# X8-Navboard.net
KiCad netlist of a schematic drawn in EAGLE
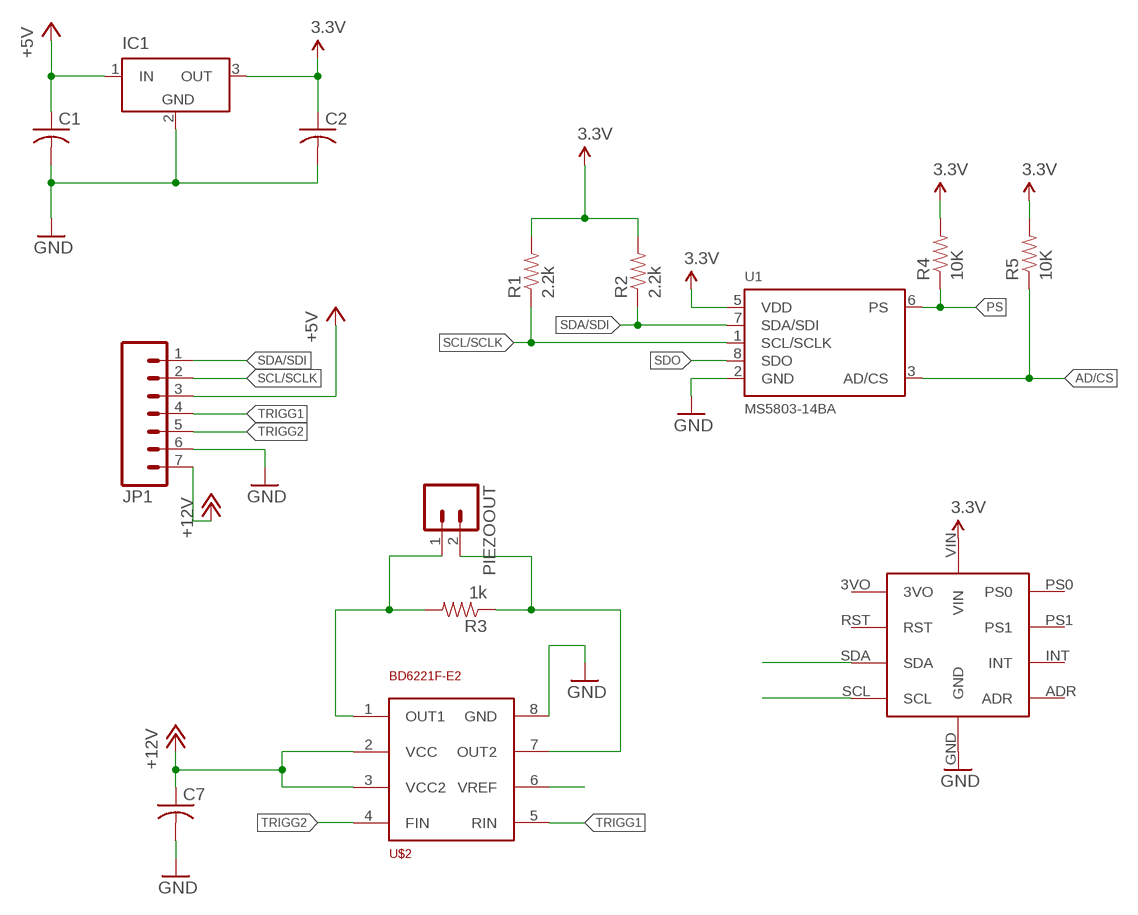
[diagram p0: schematic, sheet 1]

(export (version "E")
  (design (tool "Eeschema 10.0.6"))
  (components
    (comp (ref "C1")
      (value "C-USC0603")
      (footprint "eagle-import:C0603")
      (libsource (lib "eagle-import") (part "C-USC0603"))
    )
    (comp (ref "C2")
      (value "C-USC0603")
      (footprint "eagle-import:C0603")
      (libsource (lib "eagle-import") (part "C-USC0603"))
    )
    (comp (ref "C7")
      (value "C-USC0603")
      (footprint "eagle-import:C0603")
      (libsource (lib "eagle-import") (part "C-USC0603"))
    )
    (comp (ref "IC1")
      (value "LT1129CST5")
      (footprint "eagle-import:SOT223")
      (fields (field (name "MPN") "LT1129CST-5#PBF"))
      (libsource (lib "eagle-import") (part "LT1129CST5"))
    )
    (comp (ref "JP1")
      (value "M07")
      (footprint "eagle-import:1X07")
      (libsource (lib "eagle-import") (part "M07"))
    )
    (comp (ref "PIEZOOUT")
      (value "M02LOCK_LONGPADS")
      (footprint "eagle-import:1X02_LOCK_LONGPADS")
      (libsource (lib "eagle-import") (part "M02LOCK_LONGPADS"))
    )
    (comp (ref "R1")
      (value "2.2k")
      (footprint "eagle-import:0603-RES")
      (libsource (lib "eagle-import") (part "2.2KOHM1/10W1%(0603)"))
    )
    (comp (ref "R2")
      (value "2.2k")
      (footprint "eagle-import:0603-RES")
      (libsource (lib "eagle-import") (part "2.2KOHM1/10W1%(0603)"))
    )
    (comp (ref "R3")
      (value "1k")
      (footprint "eagle-import:0603-RES")
      (libsource (lib "eagle-import") (part "2.2KOHM1/10W1%(0603)"))
    )
    (comp (ref "R4")
      (value "10K")
      (footprint "eagle-import:0603-RES")
      (libsource (lib "eagle-import") (part "10KOHM1/10W1%(0603)0603"))
    )
    (comp (ref "R5")
      (value "10K")
      (footprint "eagle-import:0603-RES")
      (libsource (lib "eagle-import") (part "10KOHM1/10W1%(0603)0603"))
    )
    (comp (ref "U$1")
      (value "BNO055_9DOF_BREAKOUT")
      (footprint "eagle-import:BNO055")
      (libsource (lib "eagle-import") (part "BNO055_9DOF_BREAKOUT"))
    )
    (comp (ref "U$2")
      (value "BD6221F-E2")
      (footprint "eagle-import:SOIC8")
      (libsource (lib "eagle-import") (part "BD6221F-E2"))
    )
    (comp (ref "U1")
      (value "MS5803-14BA")
      (footprint "eagle-import:MS5803")
      (libsource (lib "eagle-import") (part "MS5803-14BA"))
    )
  )
  (nets
    (net (code "1") (name "+5V") (class "Default")
      (node (ref "C1") (pin "1") (pinfunction "1_1") (pintype "passive"))
      (node (ref "IC1") (pin "1") (pinfunction "IN_1") (pintype "input"))
      (node (ref "JP1") (pin "3") (pinfunction "3_3") (pintype "passive"))
    )
    (net (code "2") (name "+12V") (class "Default")
      (node (ref "C7") (pin "1") (pinfunction "1_1") (pintype "passive"))
      (node (ref "JP1") (pin "7") (pinfunction "7_7") (pintype "passive"))
      (node (ref "U$2") (pin "2") (pinfunction "VCC_2") (pintype "bidirectional"))
      (node (ref "U$2") (pin "3") (pinfunction "VCC2_3") (pintype "bidirectional"))
    )
    (net (code "3") (name "3.3V") (class "Default")
      (node (ref "C2") (pin "1") (pinfunction "1_1") (pintype "passive"))
      (node (ref "IC1") (pin "3") (pinfunction "OUT_3") (pintype "output"))
      (node (ref "R1") (pin "2") (pinfunction "2_2") (pintype "passive"))
      (node (ref "R2") (pin "2") (pinfunction "2_2") (pintype "passive"))
      (node (ref "R4") (pin "2") (pinfunction "2_2") (pintype "passive"))
      (node (ref "R5") (pin "2") (pinfunction "2_2") (pintype "passive"))
      (node (ref "U$1") (pin "VIN") (pinfunction "VIN_VIN") (pintype "bidirectional"))
      (node (ref "U1") (pin "5") (pinfunction "VDD_5") (pintype "bidirectional"))
    )
    (net (code "4") (name "AD{slash}CS") (class "Default")
      (node (ref "R5") (pin "1") (pinfunction "1_1") (pintype "passive"))
      (node (ref "U1") (pin "3") (pinfunction "AD/CS_3") (pintype "bidirectional"))
    )
    (net (code "5") (name "GND") (class "Default")
      (node (ref "C1") (pin "2") (pinfunction "2_2") (pintype "passive"))
      (node (ref "C2") (pin "2") (pinfunction "2_2") (pintype "passive"))
      (node (ref "C7") (pin "2") (pinfunction "2_2") (pintype "passive"))
      (node (ref "IC1") (pin "2") (pinfunction "GND_2") (pintype "power_in"))
      (node (ref "JP1") (pin "6") (pinfunction "6_6") (pintype "passive"))
      (node (ref "U$1") (pin "GND") (pinfunction "GND_GND") (pintype "bidirectional"))
      (node (ref "U$2") (pin "8") (pinfunction "GND_8") (pintype "bidirectional"))
      (node (ref "U1") (pin "2") (pinfunction "GND_2") (pintype "bidirectional"))
    )
    (net (code "6") (name "Net-(U$2-OUT1)") (class "Default")
      (node (ref "PIEZOOUT") (pin "1") (pinfunction "1_1") (pintype "passive"))
      (node (ref "R3") (pin "2") (pinfunction "2_2") (pintype "passive"))
      (node (ref "U$2") (pin "1") (pinfunction "OUT1_1") (pintype "bidirectional"))
    )
    (net (code "7") (name "Net-(U$2-OUT2)") (class "Default")
      (node (ref "PIEZOOUT") (pin "2") (pinfunction "2_2") (pintype "passive"))
      (node (ref "R3") (pin "1") (pinfunction "1_1") (pintype "passive"))
      (node (ref "U$2") (pin "7") (pinfunction "OUT2_7") (pintype "bidirectional"))
    )
    (net (code "8") (name "PS") (class "Default")
      (node (ref "R4") (pin "1") (pinfunction "1_1") (pintype "passive"))
      (node (ref "U1") (pin "6") (pinfunction "PS_6") (pintype "bidirectional"))
    )
    (net (code "9") (name "SCL{slash}SCLK") (class "Default")
      (node (ref "JP1") (pin "2") (pinfunction "2_2") (pintype "passive"))
      (node (ref "R1") (pin "1") (pinfunction "1_1") (pintype "passive"))
      (node (ref "U$1") (pin "SCL") (pinfunction "SCL_SCL") (pintype "bidirectional"))
      (node (ref "U1") (pin "1") (pinfunction "SCL/SCLK_1") (pintype "bidirectional"))
    )
    (net (code "10") (name "SDA{slash}SDI") (class "Default")
      (node (ref "JP1") (pin "1") (pinfunction "1_1") (pintype "passive"))
      (node (ref "R2") (pin "1") (pinfunction "1_1") (pintype "passive"))
      (node (ref "U$1") (pin "SDA") (pinfunction "SDA_SDA") (pintype "bidirectional"))
      (node (ref "U1") (pin "7") (pinfunction "SDA/SDI_7") (pintype "bidirectional"))
    )
    (net (code "11") (name "SDO") (class "Default")
      (node (ref "U1") (pin "8") (pinfunction "SDO_8") (pintype "bidirectional"))
    )
    (net (code "12") (name "TRIGG1") (class "Default")
      (node (ref "JP1") (pin "4") (pinfunction "4_4") (pintype "passive"))
      (node (ref "U$2") (pin "5") (pinfunction "RIN_5") (pintype "bidirectional"))
    )
    (net (code "13") (name "TRIGG2") (class "Default")
      (node (ref "JP1") (pin "5") (pinfunction "5_5") (pintype "passive"))
      (node (ref "U$2") (pin "4") (pinfunction "FIN_4") (pintype "bidirectional"))
    )
    (net (code "14") (name "unconnected-(U$1-Pad3VO)") (class "Default")
      (node (ref "U$1") (pin "3VO") (pinfunction "3VO_3VO") (pintype "bidirectional"))
    )
    (net (code "15") (name "unconnected-(U$1-PadADR)") (class "Default")
      (node (ref "U$1") (pin "ADR") (pinfunction "ADR_ADR") (pintype "bidirectional"))
    )
    (net (code "16") (name "unconnected-(U$1-PadINT)") (class "Default")
      (node (ref "U$1") (pin "INT") (pinfunction "INT_INT") (pintype "bidirectional"))
    )
    (net (code "17") (name "unconnected-(U$1-PadPS0)") (class "Default")
      (node (ref "U$1") (pin "PS0") (pinfunction "PS0_PS0") (pintype "bidirectional"))
    )
    (net (code "18") (name "unconnected-(U$1-PadPS1)") (class "Default")
      (node (ref "U$1") (pin "PS1") (pinfunction "PS1_PS1") (pintype "bidirectional"))
    )
    (net (code "19") (name "unconnected-(U$1-PadRST)") (class "Default")
      (node (ref "U$1") (pin "RST") (pinfunction "RST_RST") (pintype "bidirectional"))
    )
    (net (code "20") (name "unconnected-(U$2-VREF-Pad6)") (class "Default")
      (node (ref "U$2") (pin "6") (pinfunction "VREF_6") (pintype "bidirectional"))
    )
  )
)
